# SAMR21_Xplained_Pro_EDBG.net
KiCad netlist of a schematic drawn in Altium Designer
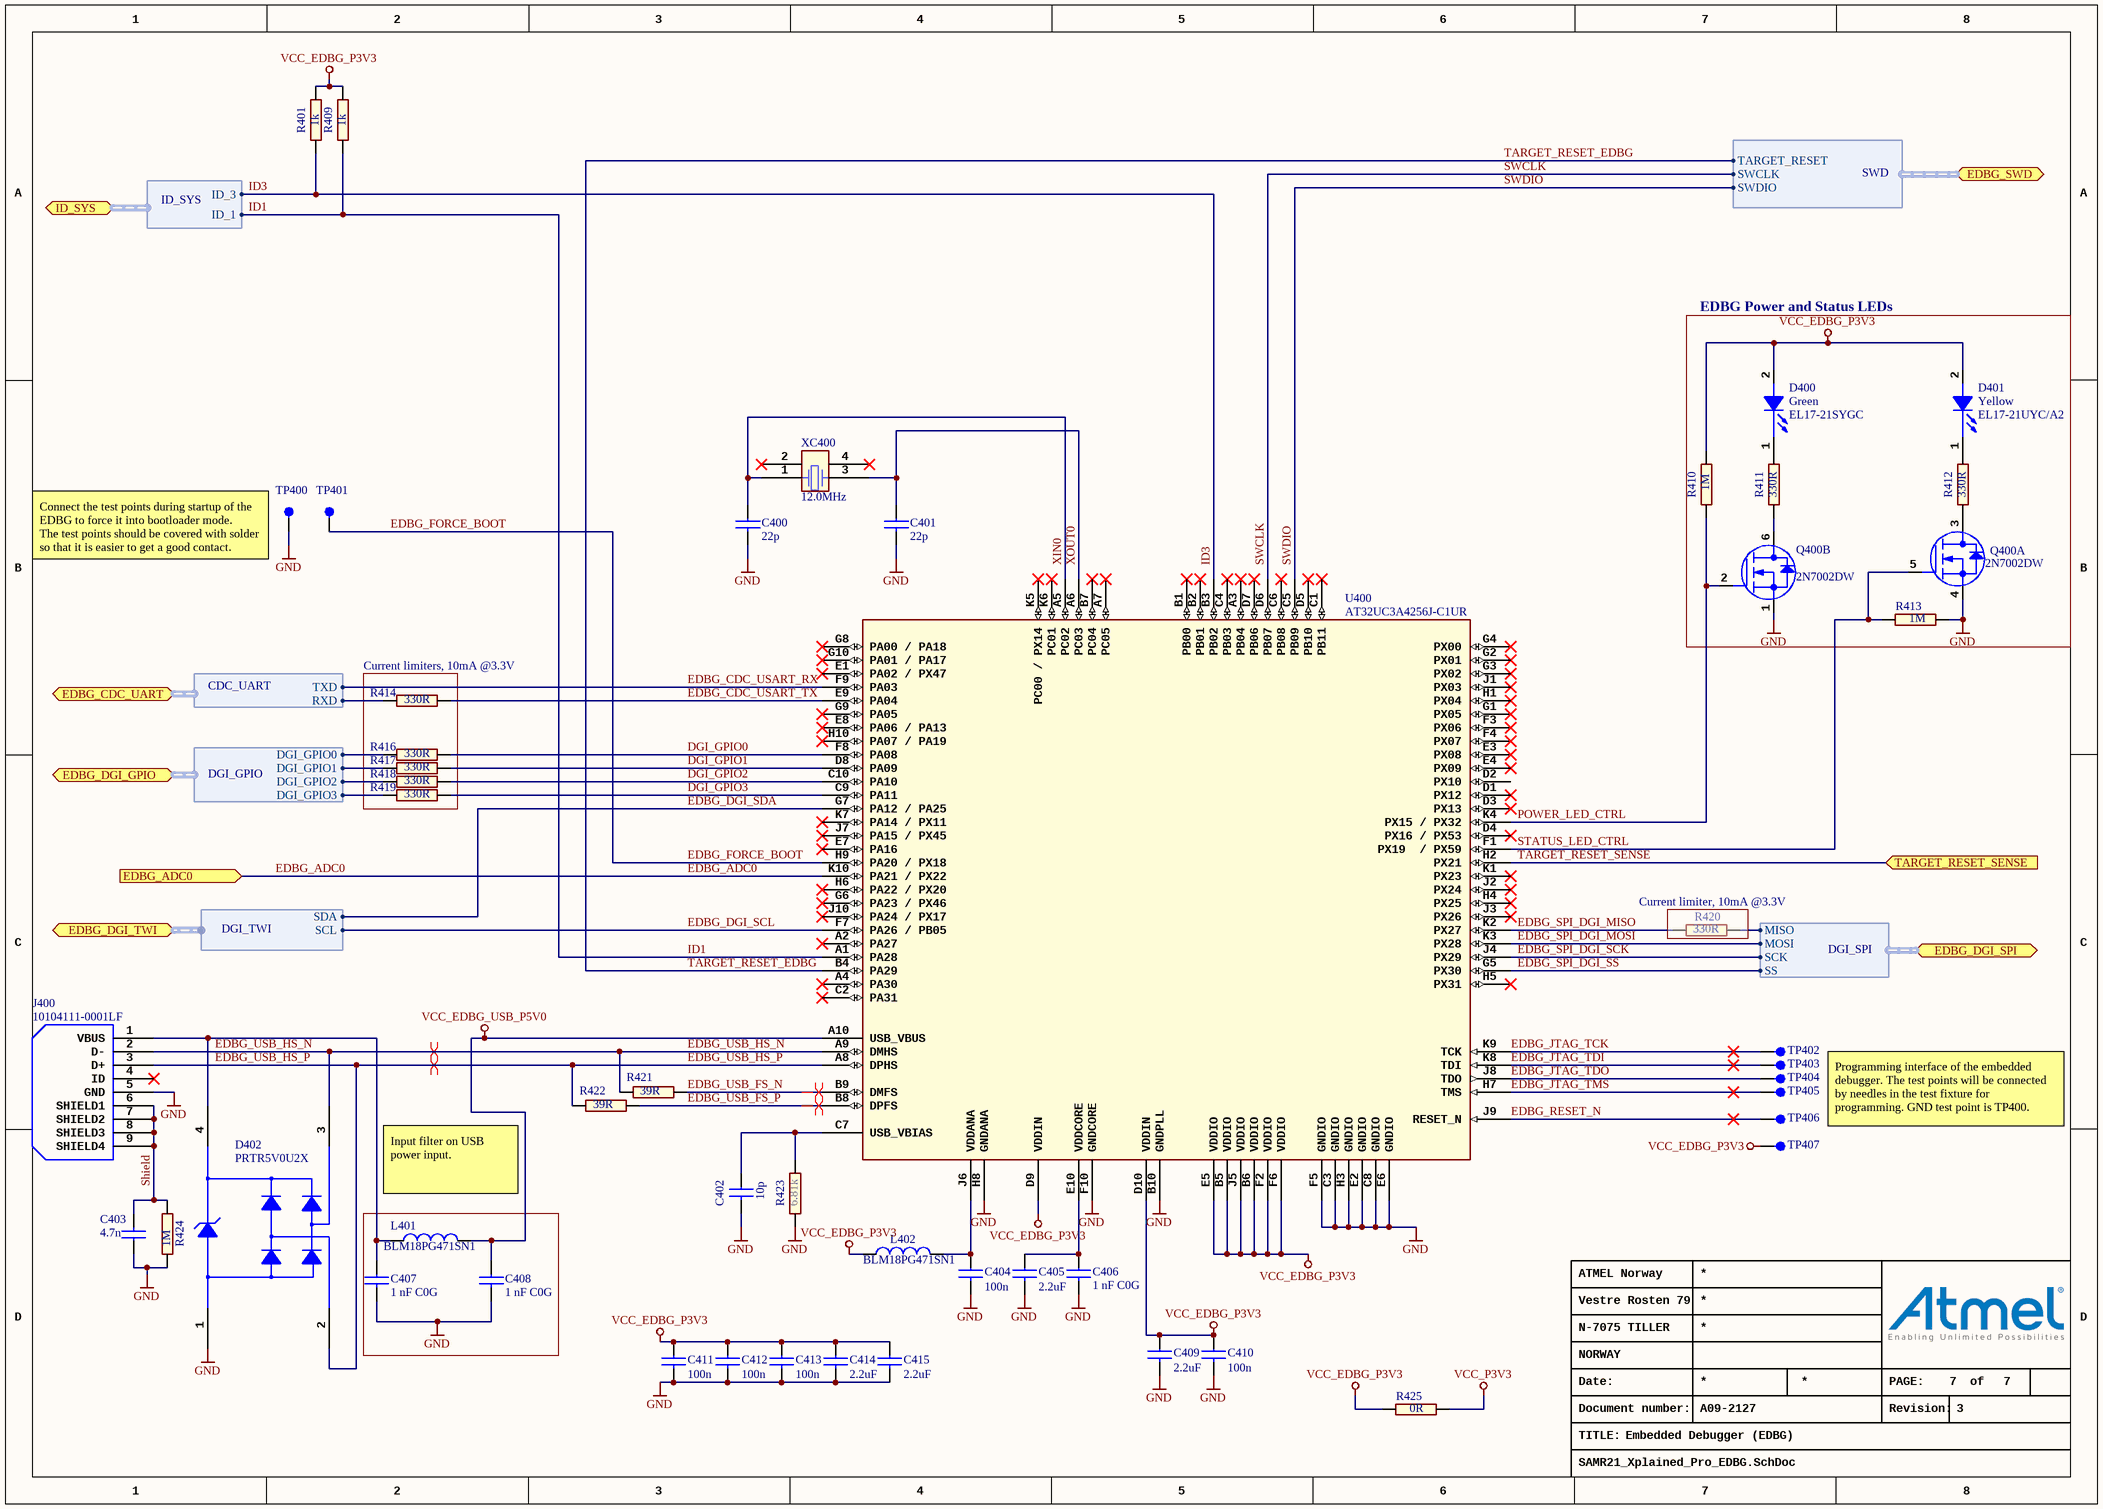
[diagram p0: SAMR21_Xplained_Pro_EDBG.SchDoc]

(export (version "E")
  (design (tool "Eeschema 10.0.6"))
  (components
    (comp (ref "C400")
      (value "22p")
      (footprint "AP1-00053")
      (description "Ceramic capacitor, SMD 0402, NP0, 50V, +/-5%")
      (fields (field (name "TOLERANCE") "50V, +/-5%"))
      (libsource (lib "AltiumDbLib") (part "CAP-NONPOL"))
    )
    (comp (ref "C401")
      (value "22p")
      (footprint "AP1-00053")
      (description "Ceramic capacitor, SMD 0402, NP0, 50V, +/-5%")
      (fields (field (name "TOLERANCE") "50V, +/-5%"))
      (libsource (lib "AltiumDbLib") (part "CAP-NONPOL"))
    )
    (comp (ref "C402")
      (value "10p")
      (footprint "AP1-00053")
      (description "Ceramic capacitor, SMD 0402, NP0, 50V, +/-5%")
      (fields (field (name "TOLERANCE") "50V, +/-5%"))
      (libsource (lib "AltiumDbLib") (part "CAP-NONPOL"))
    )
    (comp (ref "C403")
      (value "4.7n")
      (footprint "AP1-00053")
      (description "Ceramic capacitor, SMD 0402, X7R, 25V, +/-10%")
      (fields (field (name "TOLERANCE") "25V, +/-10%") (field (name "Comment") "CAP-NONPOL"))
      (libsource (lib "AltiumDbLib") (part "CAP-NONPOL"))
    )
    (comp (ref "C404")
      (value "100n")
      (footprint "AP1-00053")
      (description "Ceramic capacitor, SMD 0402, X7R, 16V, +/-10%")
      (fields (field (name "TOLERANCE") "16V, +/-10%") (field (name "MANUFACTURER") "Kemet"))
      (libsource (lib "AltiumDbLib") (part "CAP-NONPOL"))
    )
    (comp (ref "C405")
      (value "2.2uF")
      (footprint "AP1-00053")
      (description "Ceramic capacitor, SMD 0402, X5R, 6.3V, +/-20%")
      (fields (field (name "TOLERANCE") "±20%") (field (name "MANUFACTURER") "Kemet"))
      (libsource (lib "AltiumDbLib") (part "CAP-NONPOL"))
    )
    (comp (ref "C406")
      (value "1 nF C0G")
      (footprint "AP1-00053")
      (description "Ceramic capacitor, SMD 0402, C0G, 50V, +/-5%")
      (fields (field (name "TOLERANCE") "5%") (field (name "MANUFACTURER") "Murata"))
      (libsource (lib "AltiumDbLib") (part "CAP-NONPOL"))
    )
    (comp (ref "C407")
      (value "1 nF C0G")
      (footprint "AP1-00053")
      (description "Ceramic capacitor, SMD 0402, C0G, 50V, +/-5%")
      (fields (field (name "TOLERANCE") "5%") (field (name "MANUFACTURER") "Murata"))
      (libsource (lib "AltiumDbLib") (part "CAP-NONPOL"))
    )
    (comp (ref "C408")
      (value "1 nF C0G")
      (footprint "AP1-00053")
      (description "Ceramic capacitor, SMD 0402, C0G, 50V, +/-5%")
      (fields (field (name "TOLERANCE") "5%") (field (name "MANUFACTURER") "Murata"))
      (libsource (lib "AltiumDbLib") (part "CAP-NONPOL"))
    )
    (comp (ref "C409")
      (value "2.2uF")
      (footprint "AP1-00053")
      (description "Ceramic capacitor, SMD 0402, X5R, 6.3V, +/-20%")
      (fields (field (name "TOLERANCE") "±20%") (field (name "MANUFACTURER") "Kemet"))
      (libsource (lib "AltiumDbLib") (part "CAP-NONPOL"))
    )
    (comp (ref "C410")
      (value "100n")
      (footprint "AP1-00053")
      (description "Ceramic capacitor, SMD 0402, X7R, 16V, +/-10%")
      (fields (field (name "TOLERANCE") "16V, +/-10%") (field (name "MANUFACTURER") "Kemet"))
      (libsource (lib "AltiumDbLib") (part "CAP-NONPOL"))
    )
    (comp (ref "C411")
      (value "100n")
      (footprint "AP1-00053")
      (description "Ceramic capacitor, SMD 0402, X7R, 16V, +/-10%")
      (fields (field (name "TOLERANCE") "16V, +/-10%") (field (name "MANUFACTURER") "Kemet"))
      (libsource (lib "AltiumDbLib") (part "CAP-NONPOL"))
    )
    (comp (ref "C412")
      (value "100n")
      (footprint "AP1-00053")
      (description "Ceramic capacitor, SMD 0402, X7R, 16V, +/-10%")
      (fields (field (name "TOLERANCE") "16V, +/-10%") (field (name "MANUFACTURER") "Kemet"))
      (libsource (lib "AltiumDbLib") (part "CAP-NONPOL"))
    )
    (comp (ref "C413")
      (value "100n")
      (footprint "AP1-00053")
      (description "Ceramic capacitor, SMD 0402, X7R, 16V, +/-10%")
      (fields (field (name "TOLERANCE") "16V, +/-10%") (field (name "MANUFACTURER") "Kemet"))
      (libsource (lib "AltiumDbLib") (part "CAP-NONPOL"))
    )
    (comp (ref "C414")
      (value "2.2uF")
      (footprint "AP1-00053")
      (description "Ceramic capacitor, SMD 0402, X5R, 6.3V, +/-20%")
      (fields (field (name "TOLERANCE") "±20%") (field (name "MANUFACTURER") "Kemet"))
      (libsource (lib "AltiumDbLib") (part "CAP-NONPOL"))
    )
    (comp (ref "C415")
      (value "2.2uF")
      (footprint "AP1-00053")
      (description "Ceramic capacitor, SMD 0402, X5R, 6.3V, +/-20%")
      (fields (field (name "TOLERANCE") "±20%") (field (name "MANUFACTURER") "Kemet"))
      (libsource (lib "AltiumDbLib") (part "CAP-NONPOL"))
    )
    (comp (ref "D400")
      (value "Green")
      (footprint "AP4-00013")
      (description "LED, Green, Wave length=575nm, SMD 0805, ±70°")
      (fields
        (field (name "ALTIUM_VALUE") "EL17-21SYGC")
        (field (name "MANUFACTURER") "Everlight")
        (field (name "MPN") "EL17-21SYGC")
      )
      (libsource (lib "AltiumDbLib") (part "LED_12"))
    )
    (comp (ref "D401")
      (value "Yellow")
      (footprint "AP4-00013")
      (description "LED, Yellow, Wave length=591nm, SMD 0805, ±70°")
      (fields
        (field (name "ALTIUM_VALUE") "EL17-21UYC/A2")
        (field (name "MANUFACTURER") "Everlight")
        (field (name "MPN") "17-21UYC/S530-A3/TR8")
      )
      (libsource (lib "AltiumDbLib") (part "LED_12"))
    )
    (comp (ref "D402")
      (value "PRTR5V0U2X")
      (footprint "AP4-00001")
      (description "Double rail-to-rail USB ESD protection diode")
      (fields (field (name "MANUFACTURER") "Philips"))
      (libsource (lib "AltiumDbLib") (part "PRTR5V0U2X"))
    )
    (comp (ref "J400")
      (value "10104111-0001LF")
      (footprint "AP8-00604")
      (description "Micro USB AB Connector")
      (fields (field (name "MANUFACTURER") "FCI") (field (name "Comment") "USB_AB"))
      (libsource (lib "AltiumDbLib") (part "USB_AB"))
    )
    (comp (ref "L401")
      (value "BLM18PG471SN1")
      (footprint "AP3-00005")
      (description "SMD RF inductor 0603. Z=470Ohm (@100MHz), Max R(dc)=0.65Ohm, Max current=1A")
      (fields (field (name "TOLERANCE") "±25%") (field (name "MANUFACTURER") "Murata"))
      (libsource (lib "AltiumDbLib") (part "INDUCTOR"))
    )
    (comp (ref "L402")
      (value "BLM18PG471SN1")
      (footprint "AP3-00005")
      (description "SMD RF inductor 0603. Z=470Ohm (@100MHz), Max R(dc)=0.65Ohm, Max current=1A")
      (fields (field (name "TOLERANCE") "±25%") (field (name "MANUFACTURER") "Murata"))
      (libsource (lib "AltiumDbLib") (part "INDUCTOR"))
    )
    (comp (ref "Q400")
      (value "2N7002DW")
      (footprint "AP5-00001")
      (description "Dual N-Channel MOSFET, 60V, 115mA cont,RDS(ON) < 7.5 Ohm @50mA@5V, SOT-363")
      (fields
        (field (name "MANUFACTURER") "Fairchild")
        (field (name "Comment") "Same as 2N7002 but with two MOSFETs in one package")
      )
      (libsource (lib "AltiumDbLib") (part "MOSFET_DUAL_N_S2G2D1S1G1D2"))
    )
    (comp (ref "R401")
      (value "1k")
      (footprint "AP2-00000")
      (description "Thick film resistor, SMD 0402, 1/16W, 1%")
      (fields (field (name "TOLERANCE") "1 %") (field (name "Comment") "R2"))
      (libsource (lib "AltiumDbLib") (part "R2"))
    )
    (comp (ref "R409")
      (value "1k")
      (footprint "AP2-00000")
      (description "Thick film resistor, SMD 0402, 1/16W, 1%")
      (fields (field (name "TOLERANCE") "1 %") (field (name "Comment") "R2"))
      (libsource (lib "AltiumDbLib") (part "R2"))
    )
    (comp (ref "R410")
      (value "1M")
      (footprint "AP2-00000")
      (description "Thick film resistor, SMD 0402, 1/16W, 1%")
      (fields (field (name "TOLERANCE") "1 %") (field (name "MANUFACTURER") "KOA"))
      (libsource (lib "AltiumDbLib") (part "R2"))
    )
    (comp (ref "R411")
      (value "330R")
      (footprint "AP2-00000")
      (description "Thick film resistor, SMD 0402, 1/16W, 1%")
      (fields (field (name "TOLERANCE") "1 %") (field (name "Comment") "R2"))
      (libsource (lib "AltiumDbLib") (part "R2"))
    )
    (comp (ref "R412")
      (value "330R")
      (footprint "AP2-00000")
      (description "Thick film resistor, SMD 0402, 1/16W, 1%")
      (fields (field (name "TOLERANCE") "1 %") (field (name "Comment") "R2"))
      (libsource (lib "AltiumDbLib") (part "R2"))
    )
    (comp (ref "R413")
      (value "1M")
      (footprint "AP2-00000")
      (description "Thick film resistor, SMD 0402, 1/16W, 1%")
      (fields (field (name "TOLERANCE") "1 %") (field (name "MANUFACTURER") "KOA"))
      (libsource (lib "") (part "R2_2"))
    )
    (comp (ref "R414")
      (value "330R")
      (footprint "AP2-00000")
      (description "Thick film resistor, SMD 0402, 1/16W, 1%")
      (fields (field (name "TOLERANCE") "1 %") (field (name "Comment") "R2"))
      (libsource (lib "") (part "R2_1"))
    )
    (comp (ref "R416")
      (value "330R")
      (footprint "AP2-00000")
      (description "Thick film resistor, SMD 0402, 1/16W, 1%")
      (fields (field (name "TOLERANCE") "1 %") (field (name "Comment") "R2"))
      (libsource (lib "") (part "R2_1"))
    )
    (comp (ref "R417")
      (value "330R")
      (footprint "AP2-00000")
      (description "Thick film resistor, SMD 0402, 1/16W, 1%")
      (fields (field (name "TOLERANCE") "1 %") (field (name "Comment") "R2"))
      (libsource (lib "") (part "R2_1"))
    )
    (comp (ref "R418")
      (value "330R")
      (footprint "AP2-00000")
      (description "Thick film resistor, SMD 0402, 1/16W, 1%")
      (fields (field (name "TOLERANCE") "1 %") (field (name "Comment") "R2"))
      (libsource (lib "") (part "R2_1"))
    )
    (comp (ref "R419")
      (value "330R")
      (footprint "AP2-00000")
      (description "Thick film resistor, SMD 0402, 1/16W, 1%")
      (fields (field (name "TOLERANCE") "1 %") (field (name "Comment") "R2"))
      (libsource (lib "") (part "R2_1"))
    )
    (comp (ref "R420")
      (value "330R")
      (footprint "AP2-00000")
      (description "Thick film resistor, SMD 0402, 1/16W, 1%")
      (fields (field (name "TOLERANCE") "1 %") (field (name "Comment") "R2"))
      (libsource (lib "") (part "R2_1"))
    )
    (comp (ref "R421")
      (value "39R")
      (footprint "AP2-00011")
      (description "Thick film resistor, SMD 0402, 1/16W, 1%")
      (fields (field (name "TOLERANCE") "1 %") (field (name "Comment") "R2"))
      (libsource (lib "") (part "R2_3"))
    )
    (comp (ref "R422")
      (value "39R")
      (footprint "AP2-00011")
      (description "Thick film resistor, SMD 0402, 1/16W, 1%")
      (fields (field (name "TOLERANCE") "1 %") (field (name "Comment") "R2"))
      (libsource (lib "") (part "R2_3"))
    )
    (comp (ref "R423")
      (value "6.81k")
      (footprint "AP2-00011")
      (description "Thick film resistor, SMD 0402, 1/16W, 1%")
      (fields (field (name "TOLERANCE") "1%") (field (name "Comment") "R2"))
      (libsource (lib "AltiumDbLib") (part "R2"))
    )
    (comp (ref "R424")
      (value "1M")
      (footprint "AP2-00011")
      (description "Thick film resistor, SMD 0402, 1/16W, 1%")
      (fields (field (name "TOLERANCE") "1 %") (field (name "MANUFACTURER") "KOA"))
      (libsource (lib "") (part "R2_4"))
    )
    (comp (ref "R425")
      (value "0R")
      (footprint "AP2-00000")
      (description "Thick film resistor, SMD 0402, 1/16W, 1%")
      (fields (field (name "TOLERANCE") "1 %") (field (name "Comment") "R2"))
      (libsource (lib "") (part "R2_1"))
    )
    (comp (ref "TP400")
      (value "TESTPOINT")
      (footprint "AP8-00010")
      (description "Single SMD testpad")
      (libsource (lib "AltiumDbLib") (part "TESTPOINT"))
    )
    (comp (ref "TP401")
      (value "TESTPOINT")
      (footprint "AP8-00010")
      (description "Single SMD testpad")
      (libsource (lib "AltiumDbLib") (part "TESTPOINT"))
    )
    (comp (ref "TP402")
      (value "TESTPOINT")
      (footprint "AP8-00010")
      (description "Single SMD testpad")
      (libsource (lib "AltiumDbLib") (part "TESTPOINT"))
    )
    (comp (ref "TP403")
      (value "TESTPOINT")
      (footprint "AP8-00010")
      (description "Single SMD testpad")
      (libsource (lib "AltiumDbLib") (part "TESTPOINT"))
    )
    (comp (ref "TP404")
      (value "TESTPOINT")
      (footprint "AP8-00010")
      (description "Single SMD testpad")
      (libsource (lib "AltiumDbLib") (part "TESTPOINT"))
    )
    (comp (ref "TP405")
      (value "TESTPOINT")
      (footprint "AP8-00010")
      (description "Single SMD testpad")
      (libsource (lib "AltiumDbLib") (part "TESTPOINT"))
    )
    (comp (ref "TP406")
      (value "TESTPOINT")
      (footprint "AP8-00010")
      (description "Single SMD testpad")
      (libsource (lib "AltiumDbLib") (part "TESTPOINT"))
    )
    (comp (ref "TP407")
      (value "TESTPOINT")
      (footprint "AP8-00010")
      (description "Single SMD testpad")
      (libsource (lib "AltiumDbLib") (part "TESTPOINT"))
    )
    (comp (ref "U400")
      (value "AT32UC3A4256J-C1UR")
      (footprint "AP6-00206")
      (description "AVR 32-bit RISC MCU")
      (fields (field (name "MANUFACTURER") "ATMEL") (field (name "Comment") "100 ball VFBGA"))
      (libsource (lib "AltiumDbLib") (part "AT32UC3A4_VFBGA"))
    )
    (comp (ref "XC400")
      (value "12.0MHz")
      (footprint "AP7-00039")
      (description "Fox FQ5032B 12.0MHz SMD crystal 738B-12")
      (fields (field (name "TOLERANCE") "30PPM") (field (name "MANUFACTURER") "Fox  Electronics"))
      (libsource (lib "AltiumDbLib") (part "CRYSTAL1324"))
    )
  )
  (nets
    (net (code "7") (name "/DGI_GPIO0") (class "Default")
      (node (ref "R416") (pin "2") (pinfunction "2_2") (pintype "passive"))
      (node (ref "U400") (pin "F8") (pinfunction "PA08_F8") (pintype "bidirectional"))
    )
    (net (code "8") (name "/DGI_GPIO1") (class "Default")
      (node (ref "R417") (pin "2") (pinfunction "2_2") (pintype "passive"))
      (node (ref "U400") (pin "D8") (pinfunction "PA09_D8") (pintype "bidirectional"))
    )
    (net (code "9") (name "/DGI_GPIO2") (class "Default")
      (node (ref "R418") (pin "2") (pinfunction "2_2") (pintype "passive"))
      (node (ref "U400") (pin "C10") (pinfunction "PA10_C10") (pintype "bidirectional"))
    )
    (net (code "10") (name "/DGI_GPIO3") (class "Default")
      (node (ref "R419") (pin "2") (pinfunction "2_2") (pintype "passive"))
      (node (ref "U400") (pin "C9") (pinfunction "PA11_C9") (pintype "bidirectional"))
    )
    (net (code "11") (name "/EDBG_ADC0") (class "Default")
      (node (ref "U400") (pin "K10") (pinfunction "PA21_/_PX22_K10") (pintype "bidirectional"))
    )
    (net (code "12") (name "/EDBG_CDC_USART_RX") (class "Default")
      (node (ref "U400") (pin "F9") (pinfunction "PA03_F9") (pintype "bidirectional"))
    )
    (net (code "13") (name "/EDBG_CDC_USART_TX") (class "Default")
      (node (ref "R414") (pin "2") (pinfunction "2_2") (pintype "passive"))
      (node (ref "U400") (pin "E9") (pinfunction "PA04_E9") (pintype "bidirectional"))
    )
    (net (code "14") (name "/EDBG_DGI_SCL") (class "Default")
      (node (ref "U400") (pin "F7") (pinfunction "PA26_/_PB05_F7") (pintype "bidirectional"))
    )
    (net (code "15") (name "/EDBG_DGI_SDA") (class "Default")
      (node (ref "U400") (pin "G7") (pinfunction "PA12_/_PA25_G7") (pintype "bidirectional"))
    )
    (net (code "16") (name "/EDBG_FORCE_BOOT") (class "Default")
      (node (ref "TP401") (pin "1") (pinfunction "1_1") (pintype "passive"))
      (node (ref "U400") (pin "H9") (pinfunction "PA20_/_PX18_H9") (pintype "bidirectional"))
    )
    (net (code "17") (name "/EDBG_JTAG_TCK") (class "Default")
      (node (ref "TP402") (pin "1") (pinfunction "1_1") (pintype "passive"))
      (node (ref "U400") (pin "K9") (pinfunction "TCK_K9") (pintype "input"))
    )
    (net (code "18") (name "/EDBG_JTAG_TDI") (class "Default")
      (node (ref "TP403") (pin "1") (pinfunction "1_1") (pintype "passive"))
      (node (ref "U400") (pin "K8") (pinfunction "TDI_K8") (pintype "input"))
    )
    (net (code "19") (name "/EDBG_JTAG_TDO") (class "Default")
      (node (ref "TP404") (pin "1") (pinfunction "1_1") (pintype "passive"))
      (node (ref "U400") (pin "J8") (pinfunction "TDO_J8") (pintype "output"))
    )
    (net (code "20") (name "/EDBG_JTAG_TMS") (class "Default")
      (node (ref "TP405") (pin "1") (pinfunction "1_1") (pintype "passive"))
      (node (ref "U400") (pin "H7") (pinfunction "TMS_H7") (pintype "input"))
    )
    (net (code "21") (name "/EDBG_RESET_N") (class "Default")
      (node (ref "TP406") (pin "1") (pinfunction "1_1") (pintype "passive"))
      (node (ref "U400") (pin "J9") (pinfunction "RESET_N_J9") (pintype "input"))
    )
    (net (code "22") (name "/EDBG_SPI_DGI_MISO") (class "Default")
      (node (ref "R420") (pin "1") (pinfunction "1_1") (pintype "passive"))
      (node (ref "U400") (pin "K2") (pinfunction "PX27_K2") (pintype "bidirectional"))
    )
    (net (code "23") (name "/EDBG_SPI_DGI_MOSI") (class "Default")
      (node (ref "U400") (pin "K3") (pinfunction "PX28_K3") (pintype "bidirectional"))
    )
    (net (code "24") (name "/EDBG_SPI_DGI_SCK") (class "Default")
      (node (ref "U400") (pin "J4") (pinfunction "PX29_J4") (pintype "bidirectional"))
    )
    (net (code "25") (name "/EDBG_SPI_DGI_SS") (class "Default")
      (node (ref "U400") (pin "G5") (pinfunction "PX30_G5") (pintype "bidirectional"))
    )
    (net (code "26") (name "/EDBG_USB_FS_N") (class "Default")
      (node (ref "R421") (pin "2") (pinfunction "2_2") (pintype "passive"))
      (node (ref "U400") (pin "B9") (pinfunction "DMFS_B9") (pintype "bidirectional"))
    )
    (net (code "27") (name "/EDBG_USB_FS_P") (class "Default")
      (node (ref "R422") (pin "2") (pinfunction "2_2") (pintype "passive"))
      (node (ref "U400") (pin "B8") (pinfunction "DPFS_B8") (pintype "bidirectional"))
    )
    (net (code "28") (name "/EDBG_USB_HS_N") (class "Default")
      (node (ref "D402") (pin "3") (pinfunction "I/O_2_3") (pintype "passive"))
      (node (ref "J400") (pin "2") (pinfunction "D-_2") (pintype "passive"))
      (node (ref "R421") (pin "1") (pinfunction "1_1") (pintype "passive"))
      (node (ref "U400") (pin "A9") (pinfunction "DMHS_A9") (pintype "bidirectional"))
    )
    (net (code "29") (name "/EDBG_USB_HS_P") (class "Default")
      (node (ref "D402") (pin "2") (pinfunction "I/O_1_2") (pintype "passive"))
      (node (ref "J400") (pin "3") (pinfunction "D+_3") (pintype "passive"))
      (node (ref "R422") (pin "1") (pinfunction "1_1") (pintype "passive"))
      (node (ref "U400") (pin "A8") (pinfunction "DPHS_A8") (pintype "bidirectional"))
    )
    (net (code "30") (name "/ID1") (class "Default")
      (node (ref "R409") (pin "1") (pinfunction "1_1") (pintype "passive"))
      (node (ref "U400") (pin "A1") (pinfunction "PA28_A1") (pintype "bidirectional"))
    )
    (net (code "31") (name "/ID3") (class "Default")
      (node (ref "R401") (pin "1") (pinfunction "1_1") (pintype "passive"))
      (node (ref "U400") (pin "B3") (pinfunction "PB02_B3") (pintype "bidirectional"))
    )
    (net (code "32") (name "/MISO") (class "Default")
      (node (ref "R420") (pin "2") (pinfunction "2_2") (pintype "passive"))
    )
    (net (code "33") (name "/POWER_LED_CTRL") (class "Default")
      (node (ref "Q400") (pin "2") (pinfunction "G2_2") (pintype "passive"))
      (node (ref "R410") (pin "1") (pinfunction "1_1") (pintype "passive"))
      (node (ref "U400") (pin "K4") (pinfunction "PX15_/_PX32_K4") (pintype "bidirectional"))
    )
    (net (code "34") (name "/RXD") (class "Default")
      (node (ref "R414") (pin "1") (pinfunction "1_1") (pintype "passive"))
    )
    (net (code "35") (name "/STATUS_LED_CTRL") (class "Default")
      (node (ref "Q400") (pin "5") (pinfunction "G1_5") (pintype "passive"))
      (node (ref "R413") (pin "2") (pinfunction "2_2") (pintype "passive"))
      (node (ref "U400") (pin "F1") (pinfunction "PX19__/_PX59_F1") (pintype "bidirectional"))
    )
    (net (code "36") (name "/SWCLK") (class "Default")
      (node (ref "U400") (pin "D6") (pinfunction "PB07_D6") (pintype "bidirectional"))
    )
    (net (code "37") (name "/SWDIO") (class "Default")
      (node (ref "U400") (pin "C5") (pinfunction "PB09_C5") (pintype "bidirectional"))
    )
    (net (code "38") (name "/Shield") (class "Default")
      (node (ref "C403") (pin "2") (pinfunction "2_2") (pintype "passive"))
      (node (ref "J400") (pin "6") (pinfunction "SHIELD1_6") (pintype "passive"))
      (node (ref "J400") (pin "7") (pinfunction "SHIELD2_7") (pintype "passive"))
      (node (ref "J400") (pin "8") (pinfunction "SHIELD3_8") (pintype "passive"))
      (node (ref "J400") (pin "9") (pinfunction "SHIELD4_9") (pintype "passive"))
      (node (ref "R424") (pin "2") (pinfunction "2_2") (pintype "passive"))
    )
    (net (code "39") (name "/TARGET_RESET_EDBG") (class "Default")
      (node (ref "U400") (pin "B4") (pinfunction "PA29_B4") (pintype "bidirectional"))
    )
    (net (code "40") (name "/TARGET_RESET_SENSE") (class "Default")
      (node (ref "U400") (pin "H2") (pinfunction "PX21_H2") (pintype "bidirectional"))
    )
    (net (code "41") (name "/XIN0") (class "Default")
      (node (ref "C400") (pin "1") (pinfunction "1_1") (pintype "passive"))
      (node (ref "U400") (pin "A5") (pinfunction "PC02_A5") (pintype "bidirectional"))
      (node (ref "XC400") (pin "1") (pinfunction "1_1") (pintype "passive"))
    )
    (net (code "42") (name "/XOUT0") (class "Default")
      (node (ref "C401") (pin "1") (pinfunction "1_1") (pintype "passive"))
      (node (ref "U400") (pin "A6") (pinfunction "PC03_A6") (pintype "bidirectional"))
      (node (ref "XC400") (pin "3") (pinfunction "3_3") (pintype "passive"))
    )
    (net (code "49") (name "GND") (class "Default")
      (node (ref "C400") (pin "2") (pinfunction "2_2") (pintype "passive"))
      (node (ref "C401") (pin "2") (pinfunction "2_2") (pintype "passive"))
      (node (ref "C402") (pin "2") (pinfunction "2_2") (pintype "passive"))
      (node (ref "C403") (pin "1") (pinfunction "1_1") (pintype "passive"))
      (node (ref "C404") (pin "2") (pinfunction "2_2") (pintype "passive"))
      (node (ref "C405") (pin "2") (pinfunction "2_2") (pintype "passive"))
      (node (ref "C406") (pin "2") (pinfunction "2_2") (pintype "passive"))
      (node (ref "C407") (pin "2") (pinfunction "2_2") (pintype "passive"))
      (node (ref "C408") (pin "2") (pinfunction "2_2") (pintype "passive"))
      (node (ref "C409") (pin "2") (pinfunction "2_2") (pintype "passive"))
      (node (ref "C410") (pin "2") (pinfunction "2_2") (pintype "passive"))
      (node (ref "C411") (pin "2") (pinfunction "2_2") (pintype "passive"))
      (node (ref "C412") (pin "2") (pinfunction "2_2") (pintype "passive"))
      (node (ref "C413") (pin "2") (pinfunction "2_2") (pintype "passive"))
      (node (ref "C414") (pin "2") (pinfunction "2_2") (pintype "passive"))
      (node (ref "C415") (pin "2") (pinfunction "2_2") (pintype "passive"))
      (node (ref "D402") (pin "1") (pinfunction "GND_1") (pintype "passive"))
      (node (ref "J400") (pin "5") (pinfunction "GND_5") (pintype "passive"))
      (node (ref "Q400") (pin "1") (pinfunction "S2_1") (pintype "passive"))
      (node (ref "Q400") (pin "4") (pinfunction "S1_4") (pintype "passive"))
      (node (ref "R413") (pin "1") (pinfunction "1_1") (pintype "passive"))
      (node (ref "R423") (pin "1") (pinfunction "1_1") (pintype "passive"))
      (node (ref "R424") (pin "1") (pinfunction "1_1") (pintype "passive"))
      (node (ref "TP400") (pin "1") (pinfunction "1_1") (pintype "passive"))
      (node (ref "U400") (pin "B10") (pinfunction "GNDPLL_B10") (pintype "power_in"))
      (node (ref "U400") (pin "C3") (pinfunction "GNDIO_C3") (pintype "power_in"))
      (node (ref "U400") (pin "C8") (pinfunction "GNDIO_C8") (pintype "power_in"))
      (node (ref "U400") (pin "E2") (pinfunction "GNDIO_E2") (pintype "power_in"))
      (node (ref "U400") (pin "E6") (pinfunction "GNDIO_E6") (pintype "power_in"))
      (node (ref "U400") (pin "F10") (pinfunction "GNDCORE_F10") (pintype "power_in"))
      (node (ref "U400") (pin "F5") (pinfunction "GNDIO_F5") (pintype "power_in"))
      (node (ref "U400") (pin "H3") (pinfunction "GNDIO_H3") (pintype "power_in"))
      (node (ref "U400") (pin "H8") (pinfunction "GNDANA_H8") (pintype "power_in"))
    )
    (net (code "50") (name "Net-(D400-CATHODE)") (class "Default")
      (node (ref "D400") (pin "1") (pinfunction "CATHODE_1") (pintype "passive"))
      (node (ref "R411") (pin "2") (pinfunction "2_2") (pintype "passive"))
    )
    (net (code "51") (name "Net-(D401-CATHODE)") (class "Default")
      (node (ref "D401") (pin "1") (pinfunction "CATHODE_1") (pintype "passive"))
      (node (ref "R412") (pin "2") (pinfunction "2_2") (pintype "passive"))
    )
    (net (code "52") (name "Net-(D402-VCC)") (class "Default")
      (node (ref "C407") (pin "1") (pinfunction "1_1") (pintype "passive"))
      (node (ref "D402") (pin "4") (pinfunction "VCC_4") (pintype "passive"))
      (node (ref "J400") (pin "1") (pinfunction "VBUS_1") (pintype "passive"))
      (node (ref "L401") (pin "1") (pinfunction "1_1") (pintype "passive"))
    )
    (net (code "53") (name "Net-(Q400A-D1)") (class "Default")
      (node (ref "Q400") (pin "3") (pinfunction "D1_3") (pintype "passive"))
      (node (ref "R412") (pin "1") (pinfunction "1_1") (pintype "passive"))
    )
    (net (code "54") (name "Net-(Q400B-D2)") (class "Default")
      (node (ref "Q400") (pin "6") (pinfunction "D2_6") (pintype "passive"))
      (node (ref "R411") (pin "1") (pinfunction "1_1") (pintype "passive"))
    )
    (net (code "55") (name "Net-(U400-USB_VBIAS)") (class "Default")
      (node (ref "C402") (pin "1") (pinfunction "1_1") (pintype "passive"))
      (node (ref "R423") (pin "2") (pinfunction "2_2") (pintype "passive"))
      (node (ref "U400") (pin "C7") (pinfunction "USB_VBIAS_C7") (pintype "power_in"))
    )
    (net (code "56") (name "Net-(U400-VDDANA)") (class "Default")
      (node (ref "C404") (pin "1") (pinfunction "1_1") (pintype "passive"))
      (node (ref "L402") (pin "2") (pinfunction "2_2") (pintype "passive"))
      (node (ref "U400") (pin "J6") (pinfunction "VDDANA_J6") (pintype "power_in"))
    )
    (net (code "57") (name "Net-(U400-VDDCORE)") (class "Default")
      (node (ref "C405") (pin "1") (pinfunction "1_1") (pintype "passive"))
      (node (ref "C406") (pin "1") (pinfunction "1_1") (pintype "passive"))
      (node (ref "U400") (pin "E10") (pinfunction "VDDCORE_E10") (pintype "power_in"))
    )
    (net (code "58") (name "VCC_EDBG_P3V3") (class "Default")
      (node (ref "C409") (pin "1") (pinfunction "1_1") (pintype "passive"))
      (node (ref "C410") (pin "1") (pinfunction "1_1") (pintype "passive"))
      (node (ref "C411") (pin "1") (pinfunction "1_1") (pintype "passive"))
      (node (ref "C412") (pin "1") (pinfunction "1_1") (pintype "passive"))
      (node (ref "C413") (pin "1") (pinfunction "1_1") (pintype "passive"))
      (node (ref "C414") (pin "1") (pinfunction "1_1") (pintype "passive"))
      (node (ref "C415") (pin "1") (pinfunction "1_1") (pintype "passive"))
      (node (ref "D400") (pin "2") (pinfunction "ANODE_2") (pintype "passive"))
      (node (ref "D401") (pin "2") (pinfunction "ANODE_2") (pintype "passive"))
      (node (ref "L402") (pin "1") (pinfunction "1_1") (pintype "passive"))
      (node (ref "R401") (pin "2") (pinfunction "2_2") (pintype "passive"))
      (node (ref "R409") (pin "2") (pinfunction "2_2") (pintype "passive"))
      (node (ref "R410") (pin "2") (pinfunction "2_2") (pintype "passive"))
      (node (ref "R425") (pin "1") (pinfunction "1_1") (pintype "passive"))
      (node (ref "TP407") (pin "1") (pinfunction "1_1") (pintype "passive"))
      (node (ref "U400") (pin "B5") (pinfunction "VDDIO_B5") (pintype "power_in"))
      (node (ref "U400") (pin "B6") (pinfunction "VDDIO_B6") (pintype "power_in"))
      (node (ref "U400") (pin "D10") (pinfunction "VDDIN_D10") (pintype "power_in"))
      (node (ref "U400") (pin "D9") (pinfunction "VDDIN_D9") (pintype "power_in"))
      (node (ref "U400") (pin "E5") (pinfunction "VDDIO_E5") (pintype "power_in"))
      (node (ref "U400") (pin "F2") (pinfunction "VDDIO_F2") (pintype "power_in"))
      (node (ref "U400") (pin "F6") (pinfunction "VDDIO_F6") (pintype "power_in"))
      (node (ref "U400") (pin "J5") (pinfunction "VDDIO_J5") (pintype "power_in"))
    )
    (net (code "59") (name "VCC_EDBG_USB_P5V0") (class "Default")
      (node (ref "C408") (pin "1") (pinfunction "1_1") (pintype "passive"))
      (node (ref "L401") (pin "2") (pinfunction "2_2") (pintype "passive"))
      (node (ref "U400") (pin "A10") (pinfunction "USB_VBUS_A10") (pintype "power_in"))
    )
    (net (code "60") (name "VCC_P3V3") (class "Default")
      (node (ref "R425") (pin "2") (pinfunction "2_2") (pintype "passive"))
    )
    (net (code "61") (name "unconnected-(J400-ID-Pad4)") (class "Default")
      (node (ref "J400") (pin "4") (pinfunction "ID_4") (pintype "passive+no_connect"))
    )
    (net (code "62") (name "unconnected-(R416-Pad1)") (class "Default")
      (node (ref "R416") (pin "1") (pinfunction "1_1") (pintype "passive"))
    )
    (net (code "63") (name "unconnected-(R417-Pad1)") (class "Default")
      (node (ref "R417") (pin "1") (pinfunction "1_1") (pintype "passive"))
    )
    (net (code "64") (name "unconnected-(R418-Pad1)") (class "Default")
      (node (ref "R418") (pin "1") (pinfunction "1_1") (pintype "passive"))
    )
    (net (code "65") (name "unconnected-(R419-Pad1)") (class "Default")
      (node (ref "R419") (pin "1") (pinfunction "1_1") (pintype "passive"))
    )
    (net (code "66") (name "unconnected-(U400-PA00_{slash}_PA18-PadG8)") (class "Default")
      (node (ref "U400") (pin "G8") (pinfunction "PA00_/_PA18_G8") (pintype "bidirectional+no_connect"))
    )
    (net (code "67") (name "unconnected-(U400-PA01_{slash}_PA17-PadG10)") (class "Default")
      (node (ref "U400") (pin "G10") (pinfunction "PA01_/_PA17_G10") (pintype "bidirectional+no_connect"))
    )
    (net (code "68") (name "unconnected-(U400-PA02_{slash}_PX47-PadE1)") (class "Default")
      (node (ref "U400") (pin "E1") (pinfunction "PA02_/_PX47_E1") (pintype "bidirectional+no_connect"))
    )
    (net (code "69") (name "unconnected-(U400-PA05-PadG9)") (class "Default")
      (node (ref "U400") (pin "G9") (pinfunction "PA05_G9") (pintype "bidirectional+no_connect"))
    )
    (net (code "70") (name "unconnected-(U400-PA06_{slash}_PA13-PadE8)") (class "Default")
      (node (ref "U400") (pin "E8") (pinfunction "PA06_/_PA13_E8") (pintype "bidirectional+no_connect"))
    )
    (net (code "71") (name "unconnected-(U400-PA07_{slash}_PA19-PadH10)") (class "Default")
      (node (ref "U400") (pin "H10") (pinfunction "PA07_/_PA19_H10") (pintype "bidirectional+no_connect"))
    )
    (net (code "72") (name "unconnected-(U400-PA14_{slash}_PX11-PadK7)") (class "Default")
      (node (ref "U400") (pin "K7") (pinfunction "PA14_/_PX11_K7") (pintype "bidirectional+no_connect"))
    )
    (net (code "73") (name "unconnected-(U400-PA15_{slash}_PX45-PadJ7)") (class "Default")
      (node (ref "U400") (pin "J7") (pinfunction "PA15_/_PX45_J7") (pintype "bidirectional+no_connect"))
    )
    (net (code "74") (name "unconnected-(U400-PA16-PadE7)") (class "Default")
      (node (ref "U400") (pin "E7") (pinfunction "PA16_E7") (pintype "bidirectional+no_connect"))
    )
    (net (code "75") (name "unconnected-(U400-PA22_{slash}_PX20-PadH6)") (class "Default")
      (node (ref "U400") (pin "H6") (pinfunction "PA22_/_PX20_H6") (pintype "bidirectional+no_connect"))
    )
    (net (code "76") (name "unconnected-(U400-PA23_{slash}_PX46-PadG6)") (class "Default")
      (node (ref "U400") (pin "G6") (pinfunction "PA23_/_PX46_G6") (pintype "bidirectional+no_connect"))
    )
    (net (code "77") (name "unconnected-(U400-PA24_{slash}_PX17-PadJ10)") (class "Default")
      (node (ref "U400") (pin "J10") (pinfunction "PA24_/_PX17_J10") (pintype "bidirectional+no_connect"))
    )
    (net (code "78") (name "unconnected-(U400-PA27-PadA2)") (class "Default")
      (node (ref "U400") (pin "A2") (pinfunction "PA27_A2") (pintype "bidirectional+no_connect"))
    )
    (net (code "79") (name "unconnected-(U400-PA30-PadA4)") (class "Default")
      (node (ref "U400") (pin "A4") (pinfunction "PA30_A4") (pintype "bidirectional+no_connect"))
    )
    (net (code "80") (name "unconnected-(U400-PA31-PadC2)") (class "Default")
      (node (ref "U400") (pin "C2") (pinfunction "PA31_C2") (pintype "bidirectional+no_connect"))
    )
    (net (code "81") (name "unconnected-(U400-PB00-PadB1)") (class "Default")
      (node (ref "U400") (pin "B1") (pinfunction "PB00_B1") (pintype "bidirectional+no_connect"))
    )
    (net (code "82") (name "unconnected-(U400-PB01-PadB2)") (class "Default")
      (node (ref "U400") (pin "B2") (pinfunction "PB01_B2") (pintype "bidirectional+no_connect"))
    )
    (net (code "83") (name "unconnected-(U400-PB03-PadC4)") (class "Default")
      (node (ref "U400") (pin "C4") (pinfunction "PB03_C4") (pintype "bidirectional+no_connect"))
    )
    (net (code "84") (name "unconnected-(U400-PB04-PadA3)") (class "Default")
      (node (ref "U400") (pin "A3") (pinfunction "PB04_A3") (pintype "bidirectional+no_connect"))
    )
    (net (code "85") (name "unconnected-(U400-PB06-PadD7)") (class "Default")
      (node (ref "U400") (pin "D7") (pinfunction "PB06_D7") (pintype "bidirectional+no_connect"))
    )
    (net (code "86") (name "unconnected-(U400-PB08-PadC6)") (class "Default")
      (node (ref "U400") (pin "C6") (pinfunction "PB08_C6") (pintype "bidirectional+no_connect"))
    )
    (net (code "87") (name "unconnected-(U400-PB10-PadD5)") (class "Default")
      (node (ref "U400") (pin "D5") (pinfunction "PB10_D5") (pintype "bidirectional+no_connect"))
    )
    (net (code "88") (name "unconnected-(U400-PB11-PadC1)") (class "Default")
      (node (ref "U400") (pin "C1") (pinfunction "PB11_C1") (pintype "bidirectional+no_connect"))
    )
    (net (code "89") (name "unconnected-(U400-PC00_{slash}_PX14-PadK5)") (class "Default")
      (node (ref "U400") (pin "K5") (pinfunction "PC00_/_PX14_K5") (pintype "bidirectional+no_connect"))
    )
    (net (code "90") (name "unconnected-(U400-PC01-PadK6)") (class "Default")
      (node (ref "U400") (pin "K6") (pinfunction "PC01_K6") (pintype "bidirectional+no_connect"))
    )
    (net (code "91") (name "unconnected-(U400-PC04-PadB7)") (class "Default")
      (node (ref "U400") (pin "B7") (pinfunction "PC04_B7") (pintype "bidirectional+no_connect"))
    )
    (net (code "92") (name "unconnected-(U400-PC05-PadA7)") (class "Default")
      (node (ref "U400") (pin "A7") (pinfunction "PC05_A7") (pintype "bidirectional+no_connect"))
    )
    (net (code "93") (name "unconnected-(U400-PX00-PadG4)") (class "Default")
      (node (ref "U400") (pin "G4") (pinfunction "PX00_G4") (pintype "bidirectional+no_connect"))
    )
    (net (code "94") (name "unconnected-(U400-PX01-PadG2)") (class "Default")
      (node (ref "U400") (pin "G2") (pinfunction "PX01_G2") (pintype "bidirectional+no_connect"))
    )
    (net (code "95") (name "unconnected-(U400-PX02-PadG3)") (class "Default")
      (node (ref "U400") (pin "G3") (pinfunction "PX02_G3") (pintype "bidirectional+no_connect"))
    )
    (net (code "96") (name "unconnected-(U400-PX03-PadJ1)") (class "Default")
      (node (ref "U400") (pin "J1") (pinfunction "PX03_J1") (pintype "bidirectional+no_connect"))
    )
    (net (code "97") (name "unconnected-(U400-PX04-PadH1)") (class "Default")
      (node (ref "U400") (pin "H1") (pinfunction "PX04_H1") (pintype "bidirectional+no_connect"))
    )
    (net (code "98") (name "unconnected-(U400-PX05-PadG1)") (class "Default")
      (node (ref "U400") (pin "G1") (pinfunction "PX05_G1") (pintype "bidirectional+no_connect"))
    )
    (net (code "99") (name "unconnected-(U400-PX06-PadF3)") (class "Default")
      (node (ref "U400") (pin "F3") (pinfunction "PX06_F3") (pintype "bidirectional+no_connect"))
    )
    (net (code "100") (name "unconnected-(U400-PX07-PadF4)") (class "Default")
      (node (ref "U400") (pin "F4") (pinfunction "PX07_F4") (pintype "bidirectional+no_connect"))
    )
    (net (code "101") (name "unconnected-(U400-PX08-PadE3)") (class "Default")
      (node (ref "U400") (pin "E3") (pinfunction "PX08_E3") (pintype "bidirectional+no_connect"))
    )
    (net (code "102") (name "unconnected-(U400-PX09-PadE4)") (class "Default")
      (node (ref "U400") (pin "E4") (pinfunction "PX09_E4") (pintype "bidirectional+no_connect"))
    )
    (net (code "103") (name "unconnected-(U400-PX10-PadD2)") (class "Default")
      (node (ref "U400") (pin "D2") (pinfunction "PX10_D2") (pintype "bidirectional"))
    )
    (net (code "104") (name "unconnected-(U400-PX12-PadD1)") (class "Default")
      (node (ref "U400") (pin "D1") (pinfunction "PX12_D1") (pintype "bidirectional+no_connect"))
    )
    (net (code "105") (name "unconnected-(U400-PX13-PadD3)") (class "Default")
      (node (ref "U400") (pin "D3") (pinfunction "PX13_D3") (pintype "bidirectional+no_connect"))
    )
    (net (code "106") (name "unconnected-(U400-PX16_{slash}_PX53-PadD4)") (class "Default")
      (node (ref "U400") (pin "D4") (pinfunction "PX16_/_PX53_D4") (pintype "bidirectional+no_connect"))
    )
    (net (code "107") (name "unconnected-(U400-PX23-PadK1)") (class "Default")
      (node (ref "U400") (pin "K1") (pinfunction "PX23_K1") (pintype "bidirectional+no_connect"))
    )
    (net (code "108") (name "unconnected-(U400-PX24-PadJ2)") (class "Default")
      (node (ref "U400") (pin "J2") (pinfunction "PX24_J2") (pintype "bidirectional+no_connect"))
    )
    (net (code "109") (name "unconnected-(U400-PX25-PadH4)") (class "Default")
      (node (ref "U400") (pin "H4") (pinfunction "PX25_H4") (pintype "bidirectional+no_connect"))
    )
    (net (code "110") (name "unconnected-(U400-PX26-PadJ3)") (class "Default")
      (node (ref "U400") (pin "J3") (pinfunction "PX26_J3") (pintype "bidirectional+no_connect"))
    )
    (net (code "111") (name "unconnected-(U400-PX31-PadH5)") (class "Default")
      (node (ref "U400") (pin "H5") (pinfunction "PX31_H5") (pintype "bidirectional+no_connect"))
    )
    (net (code "112") (name "unconnected-(XC400-Pad2)") (class "Default")
      (node (ref "XC400") (pin "2") (pinfunction "2_2") (pintype "passive+no_connect"))
    )
    (net (code "113") (name "unconnected-(XC400-Pad4)") (class "Default")
      (node (ref "XC400") (pin "4") (pinfunction "4_4") (pintype "passive+no_connect"))
    )
  )
)
